# SCH_VTOL-FC_2024-12-10.net
KiCad netlist of a schematic drawn in EasyEDA
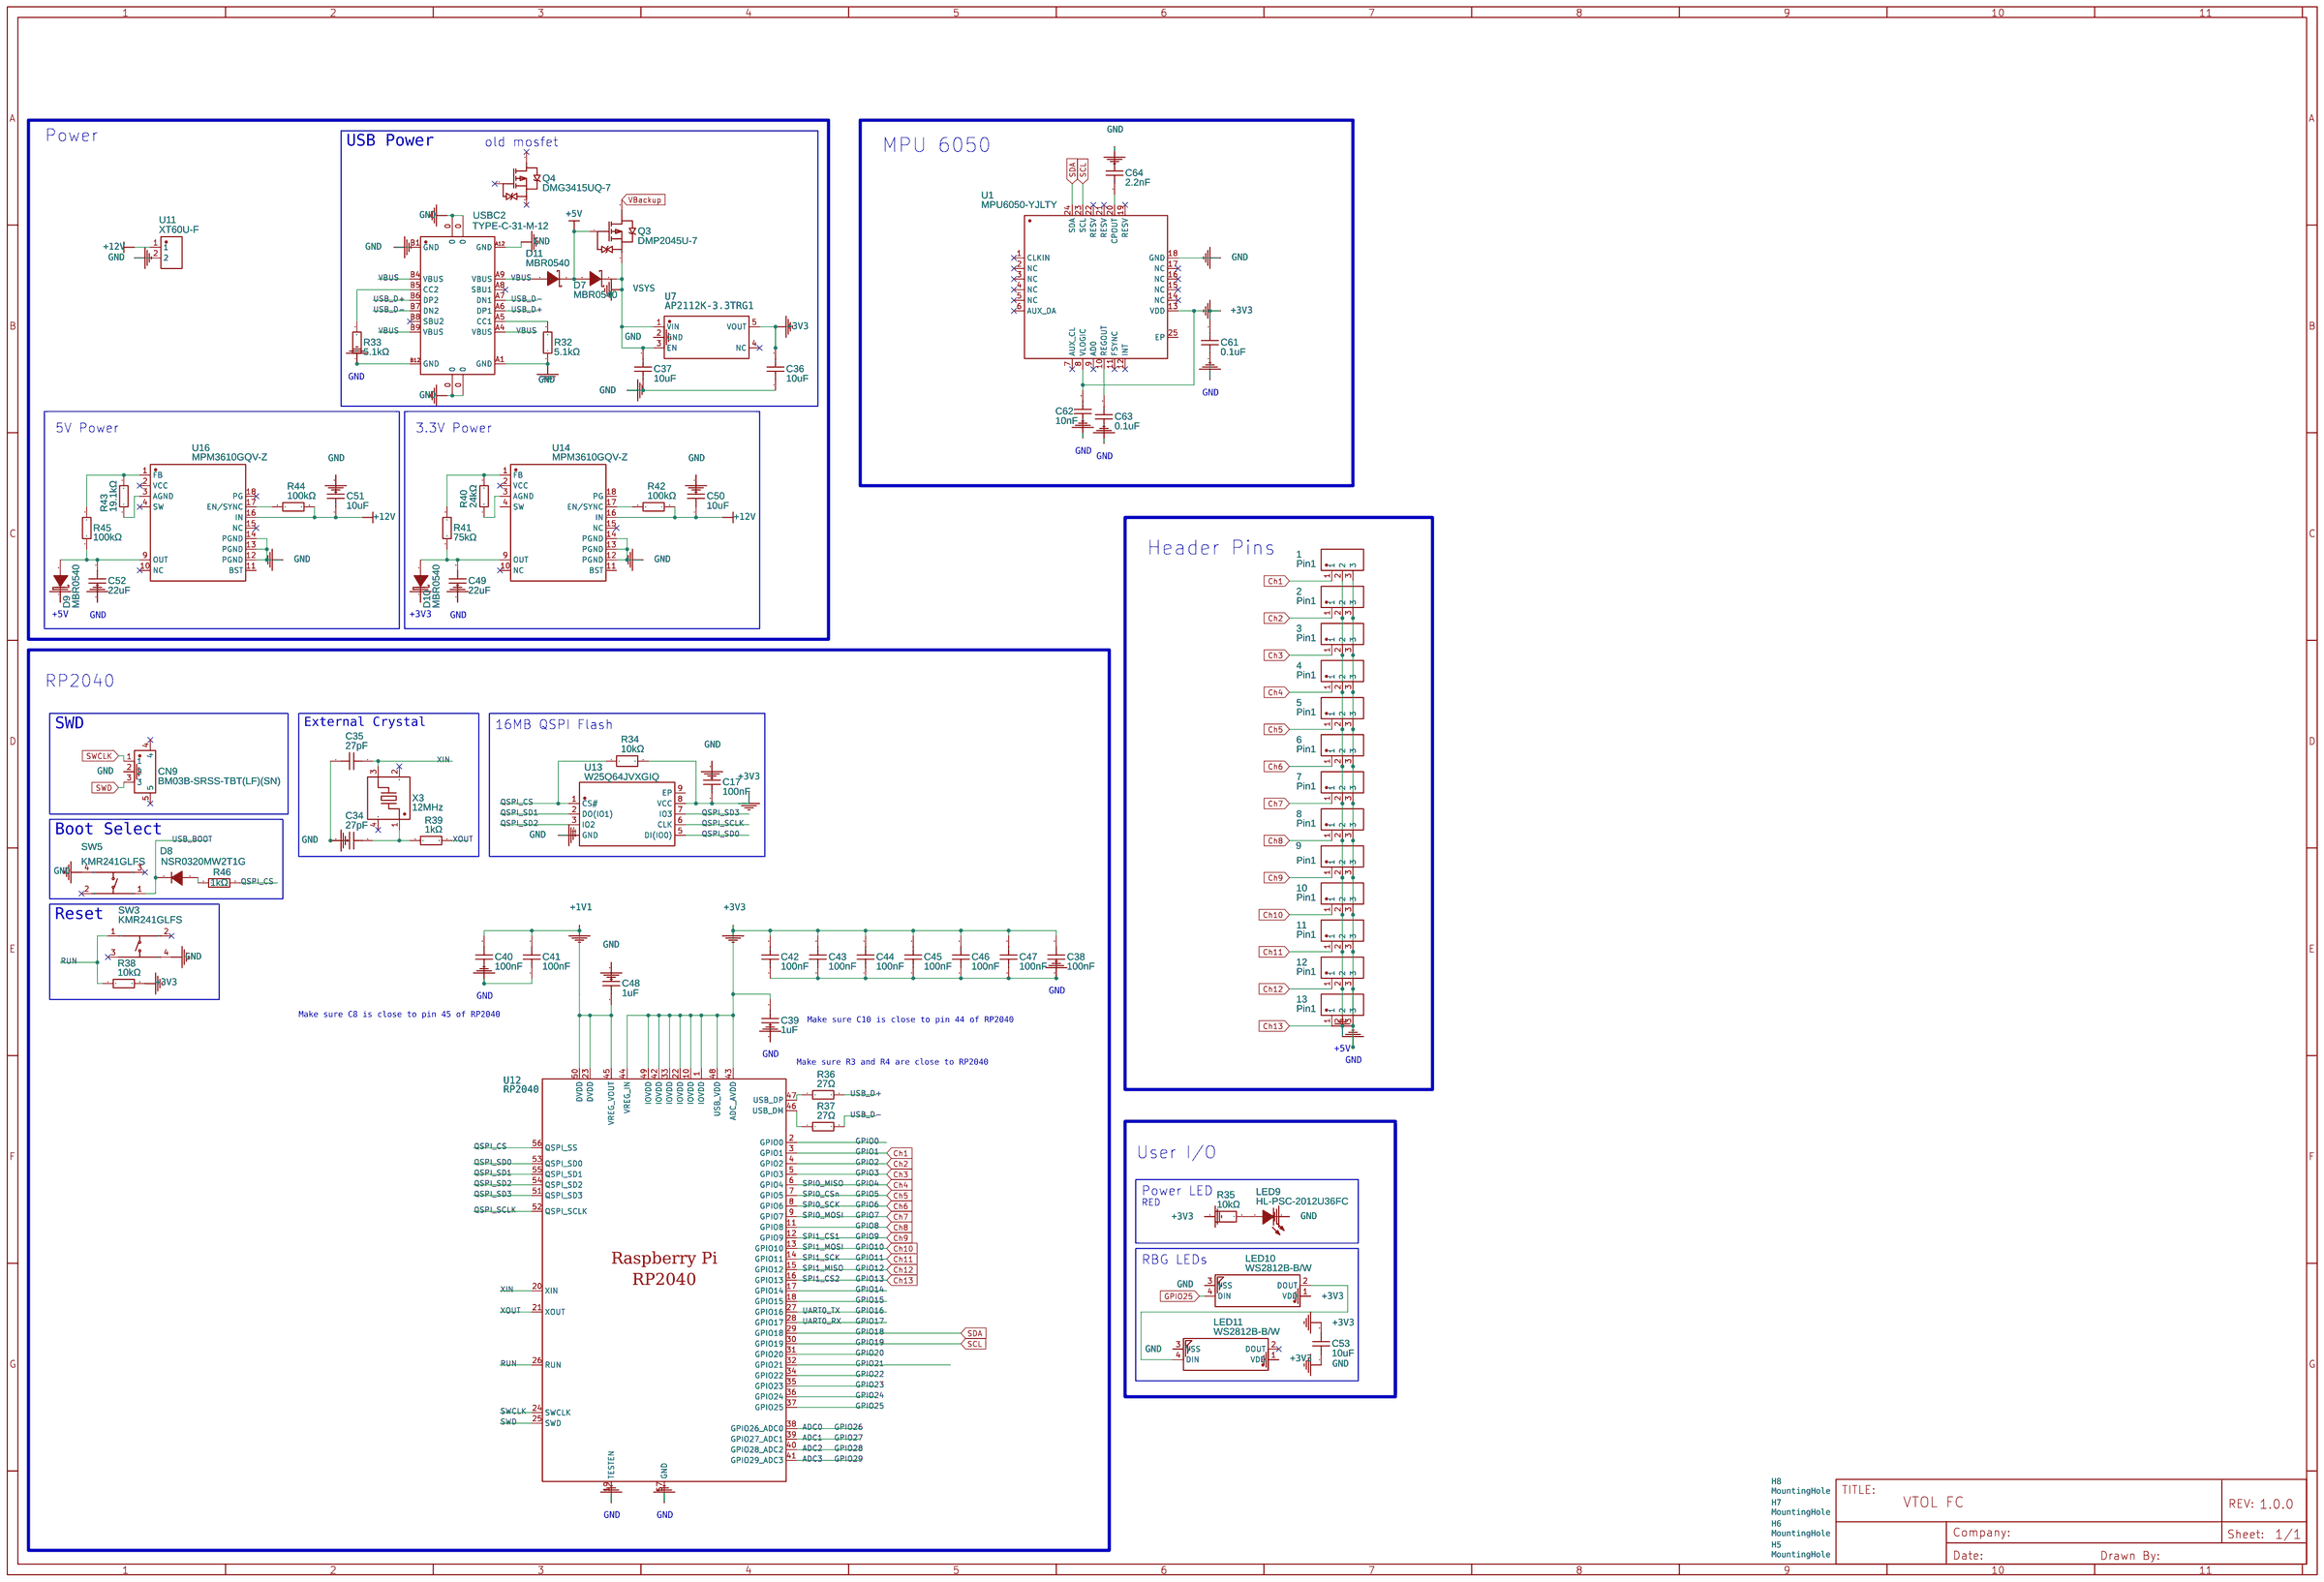
[diagram p0: schematic sheet]

(export (version "E")
  (design (tool "Eeschema 10.0.6"))
  (components
    (comp (ref "1")
      (value "Pin1")
      (fields
        (field (name "Manufacturer Part") "5-146277-3")
        (field (name "Manufacturer") "TE Connectivity(泰科电子)")
      )
      (libsource (lib "") (part "5-146277-3"))
    )
    (comp (ref "2")
      (value "Pin1")
      (fields
        (field (name "Manufacturer Part") "5-146277-3")
        (field (name "Manufacturer") "TE Connectivity(泰科电子)")
      )
      (libsource (lib "") (part "5-146277-3"))
    )
    (comp (ref "3")
      (value "Pin1")
      (fields
        (field (name "Manufacturer Part") "5-146277-3")
        (field (name "Manufacturer") "TE Connectivity(泰科电子)")
      )
      (libsource (lib "") (part "5-146277-3"))
    )
    (comp (ref "4")
      (value "Pin1")
      (fields
        (field (name "Manufacturer Part") "5-146277-3")
        (field (name "Manufacturer") "TE Connectivity(泰科电子)")
      )
      (libsource (lib "") (part "5-146277-3"))
    )
    (comp (ref "5")
      (value "Pin1")
      (fields
        (field (name "Manufacturer Part") "5-146277-3")
        (field (name "Manufacturer") "TE Connectivity(泰科电子)")
      )
      (libsource (lib "") (part "5-146277-3"))
    )
    (comp (ref "6")
      (value "Pin1")
      (fields
        (field (name "Manufacturer Part") "5-146277-3")
        (field (name "Manufacturer") "TE Connectivity(泰科电子)")
      )
      (libsource (lib "") (part "5-146277-3"))
    )
    (comp (ref "7")
      (value "Pin1")
      (fields
        (field (name "Manufacturer Part") "5-146277-3")
        (field (name "Manufacturer") "TE Connectivity(泰科电子)")
      )
      (libsource (lib "") (part "5-146277-3"))
    )
    (comp (ref "8")
      (value "Pin1")
      (fields
        (field (name "Manufacturer Part") "5-146277-3")
        (field (name "Manufacturer") "TE Connectivity(泰科电子)")
      )
      (libsource (lib "") (part "5-146277-3"))
    )
    (comp (ref "9")
      (value "Pin1")
      (fields
        (field (name "Manufacturer Part") "5-146277-3")
        (field (name "Manufacturer") "TE Connectivity(泰科电子)")
      )
      (libsource (lib "") (part "5-146277-3"))
    )
    (comp (ref "10")
      (value "Pin1")
      (fields
        (field (name "Manufacturer Part") "5-146277-3")
        (field (name "Manufacturer") "TE Connectivity(泰科电子)")
      )
      (libsource (lib "") (part "5-146277-3"))
    )
    (comp (ref "11")
      (value "Pin1")
      (fields
        (field (name "Manufacturer Part") "5-146277-3")
        (field (name "Manufacturer") "TE Connectivity(泰科电子)")
      )
      (libsource (lib "") (part "5-146277-3"))
    )
    (comp (ref "12")
      (value "Pin1")
      (fields
        (field (name "Manufacturer Part") "5-146277-3")
        (field (name "Manufacturer") "TE Connectivity(泰科电子)")
      )
      (libsource (lib "") (part "5-146277-3"))
    )
    (comp (ref "13")
      (value "Pin1")
      (fields
        (field (name "Manufacturer Part") "5-146277-3")
        (field (name "Manufacturer") "TE Connectivity(泰科电子)")
      )
      (libsource (lib "") (part "5-146277-3"))
    )
    (comp (ref "C17")
      (value "100nF")
      (fields
        (field (name "Manufacturer Part") "GCM155R71C104KA55D")
        (field (name "Manufacturer") "muRata(村田)")
      )
      (libsource (lib "") (part "GCM155R71C104KA55D"))
    )
    (comp (ref "C34")
      (value "27pF")
      (fields
        (field (name "Manufacturer Part") "GJM1555C1H270JB01D")
        (field (name "Manufacturer") "muRata(村田)")
      )
      (libsource (lib "") (part "GJM1555C1H270JB01D"))
    )
    (comp (ref "C35")
      (value "27pF")
      (fields
        (field (name "Manufacturer Part") "GJM1555C1H270JB01D")
        (field (name "Manufacturer") "muRata(村田)")
      )
      (libsource (lib "") (part "GJM1555C1H270JB01D"))
    )
    (comp (ref "C36")
      (value "10uF")
      (fields
        (field (name "Manufacturer Part") "CSA0603X5R106M6R3JT")
        (field (name "Manufacturer") "HRE(芯声)")
      )
      (libsource (lib "") (part "CSA0603X5R106M6R3JT"))
    )
    (comp (ref "C37")
      (value "10uF")
      (fields
        (field (name "Manufacturer Part") "CSA0603X5R106M6R3JT")
        (field (name "Manufacturer") "HRE(芯声)")
      )
      (libsource (lib "") (part "CSA0603X5R106M6R3JT"))
    )
    (comp (ref "C38")
      (value "100nF")
      (fields
        (field (name "Manufacturer Part") "GCM155R71C104KA55D")
        (field (name "Manufacturer") "muRata(村田)")
      )
      (libsource (lib "") (part "GCM155R71C104KA55D"))
    )
    (comp (ref "C39")
      (value "1uF")
      (fields
        (field (name "Manufacturer Part") "TCC0402X5R105K100AT")
        (field (name "Manufacturer") "CCTC(三环)")
      )
      (libsource (lib "") (part "TCC0402X5R105K100AT_1"))
    )
    (comp (ref "C40")
      (value "100nF")
      (fields
        (field (name "Manufacturer Part") "GCM155R71C104KA55D")
        (field (name "Manufacturer") "muRata(村田)")
      )
      (libsource (lib "") (part "GCM155R71C104KA55D"))
    )
    (comp (ref "C41")
      (value "100nF")
      (fields
        (field (name "Manufacturer Part") "GCM155R71C104KA55D")
        (field (name "Manufacturer") "muRata(村田)")
      )
      (libsource (lib "") (part "GCM155R71C104KA55D"))
    )
    (comp (ref "C42")
      (value "100nF")
      (fields
        (field (name "Manufacturer Part") "GCM155R71C104KA55D")
        (field (name "Manufacturer") "muRata(村田)")
      )
      (libsource (lib "") (part "GCM155R71C104KA55D"))
    )
    (comp (ref "C43")
      (value "100nF")
      (fields
        (field (name "Manufacturer Part") "GCM155R71C104KA55D")
        (field (name "Manufacturer") "muRata(村田)")
      )
      (libsource (lib "") (part "GCM155R71C104KA55D"))
    )
    (comp (ref "C44")
      (value "100nF")
      (fields
        (field (name "Manufacturer Part") "GCM155R71C104KA55D")
        (field (name "Manufacturer") "muRata(村田)")
      )
      (libsource (lib "") (part "GCM155R71C104KA55D"))
    )
    (comp (ref "C45")
      (value "100nF")
      (fields
        (field (name "Manufacturer Part") "GCM155R71C104KA55D")
        (field (name "Manufacturer") "muRata(村田)")
      )
      (libsource (lib "") (part "GCM155R71C104KA55D"))
    )
    (comp (ref "C46")
      (value "100nF")
      (fields
        (field (name "Manufacturer Part") "GCM155R71C104KA55D")
        (field (name "Manufacturer") "muRata(村田)")
      )
      (libsource (lib "") (part "GCM155R71C104KA55D"))
    )
    (comp (ref "C47")
      (value "100nF")
      (fields
        (field (name "Manufacturer Part") "GCM155R71C104KA55D")
        (field (name "Manufacturer") "muRata(村田)")
      )
      (libsource (lib "") (part "GCM155R71C104KA55D"))
    )
    (comp (ref "C48")
      (value "1uF")
      (fields
        (field (name "Manufacturer Part") "TCC0402X5R105K100AT")
        (field (name "Manufacturer") "CCTC(三环)")
      )
      (libsource (lib "") (part "TCC0402X5R105K100AT"))
    )
    (comp (ref "C49")
      (value "22uF")
      (fields
        (field (name "Manufacturer Part") "CL10A226MQ8NRNC")
        (field (name "Manufacturer") "SAMSUNG(三星)")
      )
      (libsource (lib "") (part "CL10A226MQ8NRNC"))
    )
    (comp (ref "C50")
      (value "10uF")
      (fields
        (field (name "Manufacturer Part") "CSA0603X5R106M6R3JT")
        (field (name "Manufacturer") "HRE(芯声)")
      )
      (libsource (lib "") (part "CSA0603X5R106M6R3JT"))
    )
    (comp (ref "C51")
      (value "10uF")
      (fields
        (field (name "Manufacturer Part") "CSA0603X5R106M6R3JT")
        (field (name "Manufacturer") "HRE(芯声)")
      )
      (libsource (lib "") (part "CSA0603X5R106M6R3JT"))
    )
    (comp (ref "C52")
      (value "22uF")
      (fields
        (field (name "Manufacturer Part") "CL10A226MQ8NRNC")
        (field (name "Manufacturer") "SAMSUNG(三星)")
      )
      (libsource (lib "") (part "CL10A226MQ8NRNC"))
    )
    (comp (ref "C53")
      (value "10uF")
      (fields
        (field (name "Manufacturer Part") "CSA0603X5R106M6R3JT")
        (field (name "Manufacturer") "HRE(芯声)")
      )
      (libsource (lib "") (part "CSA0603X5R106M6R3JT"))
    )
    (comp (ref "C61")
      (value "0.1uF")
      (fields (field (name "Manufacturer Part") "0603"))
      (libsource (lib "") (part "0603_C9900021180_1"))
    )
    (comp (ref "C62")
      (value "10nF")
      (fields (field (name "Manufacturer Part") "0603"))
      (libsource (lib "") (part "0603_C9900021180_1"))
    )
    (comp (ref "C63")
      (value "0.1uF")
      (fields (field (name "Manufacturer Part") "0603"))
      (libsource (lib "") (part "0603_C9900021180_1"))
    )
    (comp (ref "C64")
      (value "2.2nF")
      (fields (field (name "Manufacturer Part") "0603"))
      (libsource (lib "") (part "0603_C9900021180"))
    )
    (comp (ref "CN9")
      (value "BM03B-SRSS-TBT(LF)(SN)")
      (fields (field (name "Manufacturer") "JST"))
      (libsource (lib "") (part "BM03B-SRSS-TBT(LF)(SN)"))
    )
    (comp (ref "D7")
      (value "MBR0540")
      (fields (field (name "Manufacturer") "SHIKUES(时科)"))
      (libsource (lib "") (part "MBR0540"))
    )
    (comp (ref "D8")
      (value "NSR0320MW2T1G")
      (fields (field (name "Manufacturer") "onsemi(安森美)"))
      (libsource (lib "") (part "NSR0320MW2T1G"))
    )
    (comp (ref "D9")
      (value "MBR0540")
      (fields (field (name "Manufacturer") "SHIKUES(时科)"))
      (libsource (lib "") (part "MBR0540_1"))
    )
    (comp (ref "D10")
      (value "MBR0540")
      (fields (field (name "Manufacturer") "SHIKUES(时科)"))
      (libsource (lib "") (part "MBR0540_1"))
    )
    (comp (ref "D11")
      (value "MBR0540")
      (fields (field (name "Manufacturer") "SHIKUES(时科)"))
      (libsource (lib "") (part "MBR0540"))
    )
    (comp (ref "H5") (value "MountingHole") (libsource (lib "") (part "Unknown_1650_-25")))
    (comp (ref "H6") (value "MountingHole") (libsource (lib "") (part "Unknown_1650_-45")))
    (comp (ref "H7") (value "MountingHole") (libsource (lib "") (part "Unknown_1650_-65")))
    (comp (ref "H8") (value "MountingHole") (libsource (lib "") (part "Unknown_1650_-85")))
    (comp (ref "LED9")
      (value "HL-PSC-2012U36FC")
      (fields (field (name "Manufacturer") "HONGLITRONIC(鸿利光电)"))
      (libsource (lib "") (part "HL-PSC-2012U36FC"))
    )
    (comp (ref "LED10")
      (value "WS2812B-B/W")
      (fields (field (name "Manufacturer Part") "WS2812B-B/T") (field (name "Manufacturer") "worldsemi"))
      (libsource (lib "") (part "WS2812B-B/W"))
    )
    (comp (ref "LED11")
      (value "WS2812B-B/W")
      (fields (field (name "Manufacturer Part") "WS2812B-B/T") (field (name "Manufacturer") "worldsemi"))
      (libsource (lib "") (part "WS2812B-B/W"))
    )
    (comp (ref "Q3")
      (value "DMP2045U-7")
      (fields (field (name "Manufacturer") "DIODES(美台)"))
      (libsource (lib "") (part "DMP2045U-7"))
    )
    (comp (ref "Q4")
      (value "DMG3415UQ-7")
      (fields (field (name "Manufacturer") "DIODES(美台)"))
      (libsource (lib "") (part "DMG3415UQ-7"))
    )
    (comp (ref "R32")
      (value "5.1kΩ")
      (fields (field (name "Manufacturer Part") "ARG03DTC5101") (field (name "Manufacturer") "Viking(光颉)"))
      (libsource (lib "") (part "ARG03DTC5101"))
    )
    (comp (ref "R33")
      (value "5.1kΩ")
      (fields (field (name "Manufacturer Part") "ARG03DTC5101") (field (name "Manufacturer") "Viking(光颉)"))
      (libsource (lib "") (part "ARG03DTC5101"))
    )
    (comp (ref "R34")
      (value "10kΩ")
      (fields (field (name "Manufacturer Part") "FRC0603F1002TS") (field (name "Manufacturer") "FOJAN(富捷)"))
      (libsource (lib "") (part "FRC0603F1002TS"))
    )
    (comp (ref "R35")
      (value "10kΩ")
      (fields (field (name "Manufacturer Part") "FRC0603F1002TS") (field (name "Manufacturer") "FOJAN(富捷)"))
      (libsource (lib "") (part "FRC0603F1002TS"))
    )
    (comp (ref "R36")
      (value "27Ω")
      (fields
        (field (name "Manufacturer Part") "0402WGJ0270TCE")
        (field (name "Manufacturer") "UNI-ROYAL(厚声)")
      )
      (libsource (lib "") (part "0402WGJ0270TCE"))
    )
    (comp (ref "R37")
      (value "27Ω")
      (fields
        (field (name "Manufacturer Part") "0402WGJ0270TCE")
        (field (name "Manufacturer") "UNI-ROYAL(厚声)")
      )
      (libsource (lib "") (part "0402WGJ0270TCE"))
    )
    (comp (ref "R38")
      (value "10kΩ")
      (fields
        (field (name "Manufacturer Part") "0603WAF1002T5E")
        (field (name "Manufacturer") "UNI-ROYAL(厚声)")
      )
      (libsource (lib "") (part "0603WAF1002T5E"))
    )
    (comp (ref "R39")
      (value "1kΩ")
      (fields
        (field (name "Manufacturer Part") "0603WAF1001T5E")
        (field (name "Manufacturer") "UNI-ROYAL(厚声)")
      )
      (libsource (lib "") (part "0603WAF1001T5E"))
    )
    (comp (ref "R40")
      (value "24kΩ")
      (fields
        (field (name "Manufacturer Part") "0603WAF2402T5E")
        (field (name "Manufacturer") "UNI-ROYAL(厚声)")
      )
      (libsource (lib "") (part "0603WAF2402T5E"))
    )
    (comp (ref "R41")
      (value "75kΩ")
      (fields
        (field (name "Manufacturer Part") "0603WAF7502T5E")
        (field (name "Manufacturer") "UNI-ROYAL(厚声)")
      )
      (libsource (lib "") (part "0603WAF7502T5E"))
    )
    (comp (ref "R42")
      (value "100kΩ")
      (fields
        (field (name "Manufacturer Part") "0603WAF1003T5E")
        (field (name "Manufacturer") "UNI-ROYAL(厚声)")
      )
      (libsource (lib "") (part "0603WAF1003T5E"))
    )
    (comp (ref "R43")
      (value "19.1kΩ")
      (fields
        (field (name "Manufacturer Part") "RMC060319.1K1%N")
        (field (name "Manufacturer") "Tyohm(幸亚电阻)")
      )
      (libsource (lib "") (part "RMC060319.1K1%N"))
    )
    (comp (ref "R44")
      (value "100kΩ")
      (fields
        (field (name "Manufacturer Part") "0603WAF1003T5E")
        (field (name "Manufacturer") "UNI-ROYAL(厚声)")
      )
      (libsource (lib "") (part "0603WAF1003T5E"))
    )
    (comp (ref "R45")
      (value "100kΩ")
      (fields
        (field (name "Manufacturer Part") "0603WAF1003T5E")
        (field (name "Manufacturer") "UNI-ROYAL(厚声)")
      )
      (libsource (lib "") (part "0603WAF1003T5E_1"))
    )
    (comp (ref "R46")
      (value "1kΩ")
      (fields
        (field (name "Manufacturer Part") "0603WAF1001T5E")
        (field (name "Manufacturer") "UNI-ROYAL(厚声)")
      )
      (libsource (lib "") (part "0603WAF1001T5E"))
    )
    (comp (ref "SW3")
      (value "KMR241GLFS")
      (fields (field (name "Manufacturer") "C&K"))
      (libsource (lib "") (part "KMR241GLFS_1"))
    )
    (comp (ref "SW5")
      (value "KMR241GLFS")
      (fields (field (name "Manufacturer") "C&K"))
      (libsource (lib "") (part "KMR241GLFS"))
    )
    (comp (ref "U1") (value "MPU6050-YJLTY") (libsource (lib "") (part "MPU6050-YJLTY")))
    (comp (ref "U7")
      (value "AP2112K-3.3TRG1")
      (fields (field (name "Manufacturer") "DIODES"))
      (libsource (lib "") (part "AP2112K-3.3TRG1"))
    )
    (comp (ref "U11")
      (value "XT60U-F")
      (fields (field (name "Manufacturer") "AMASS(艾迈斯)"))
      (libsource (lib "") (part "XT60U-F"))
    )
    (comp (ref "U12")
      (value "RP2040")
      (fields (field (name "Manufacturer") "Raspberry Pi(树莓派)"))
      (libsource (lib "") (part "RP2040"))
    )
    (comp (ref "U13")
      (value "W25Q64JVXGIQ")
      (fields (field (name "Manufacturer") "WINBOND(华邦)"))
      (libsource (lib "") (part "W25Q64JVXGIQ"))
    )
    (comp (ref "U14")
      (value "MPM3610GQV-Z")
      (fields (field (name "Manufacturer") "MPS(芯源)"))
      (libsource (lib "") (part "MPM3610GQV-Z"))
    )
    (comp (ref "U16")
      (value "MPM3610GQV-Z")
      (fields (field (name "Manufacturer") "MPS(芯源)"))
      (libsource (lib "") (part "MPM3610GQV-Z"))
    )
    (comp (ref "USBC2")
      (value "TYPE-C-31-M-12")
      (fields (field (name "Manufacturer") "Rectangular Connectors - Contacts"))
      (libsource (lib "") (part "TYPE-C-31-M-12"))
    )
    (comp (ref "X3")
      (value "12MHz")
      (fields
        (field (name "Manufacturer Part") "NX3225SA-12MHz-STD-CSR-6")
        (field (name "Manufacturer") "NDK")
      )
      (libsource (lib "") (part "NX3225SA-12MHZ-STD-CSR-6"))
    )
  )
  (nets
    (net (code "1") (name "+1V1") (class "Default")
      (node (ref "C40") (pin "2") (pinfunction "2_2") (pintype "unspecified"))
      (node (ref "C41") (pin "2") (pinfunction "2_2") (pintype "unspecified"))
      (node (ref "C48") (pin "2") (pinfunction "2_2") (pintype "unspecified"))
      (node (ref "U12") (pin "23") (pinfunction "DVDD_23") (pintype "bidirectional"))
      (node (ref "U12") (pin "45") (pinfunction "VREG_VOUT_45") (pintype "bidirectional"))
      (node (ref "U12") (pin "50") (pinfunction "DVDD_50") (pintype "bidirectional"))
    )
    (net (code "2") (name "+3V3") (class "Default")
      (node (ref "C17") (pin "1") (pinfunction "1_1") (pintype "unspecified"))
      (node (ref "C36") (pin "2") (pinfunction "2_2") (pintype "unspecified"))
      (node (ref "C38") (pin "2") (pinfunction "2_2") (pintype "unspecified"))
      (node (ref "C39") (pin "2") (pinfunction "2_2") (pintype "unspecified"))
      (node (ref "C42") (pin "2") (pinfunction "2_2") (pintype "unspecified"))
      (node (ref "C43") (pin "2") (pinfunction "2_2") (pintype "unspecified"))
      (node (ref "C44") (pin "2") (pinfunction "2_2") (pintype "unspecified"))
      (node (ref "C45") (pin "2") (pinfunction "2_2") (pintype "unspecified"))
      (node (ref "C46") (pin "2") (pinfunction "2_2") (pintype "unspecified"))
      (node (ref "C47") (pin "2") (pinfunction "2_2") (pintype "unspecified"))
      (node (ref "C53") (pin "2") (pinfunction "2_2") (pintype "unspecified"))
      (node (ref "C61") (pin "2") (pinfunction "2_2") (pintype "unspecified"))
      (node (ref "C62") (pin "2") (pinfunction "2_2") (pintype "unspecified"))
      (node (ref "D10") (pin "1") (pinfunction "K_1") (pintype "unspecified"))
      (node (ref "LED10") (pin "1") (pinfunction "VDD_1") (pintype "unspecified"))
      (node (ref "LED11") (pin "1") (pinfunction "VDD_1") (pintype "unspecified"))
      (node (ref "R34") (pin "2") (pinfunction "2_2") (pintype "unspecified"))
      (node (ref "R35") (pin "1") (pinfunction "1_1") (pintype "unspecified"))
      (node (ref "R38") (pin "2") (pinfunction "2_2") (pintype "input"))
      (node (ref "U1") (pin "13") (pinfunction "VDD_13") (pintype "unspecified"))
      (node (ref "U1") (pin "8") (pinfunction "VLOGIC_8") (pintype "unspecified"))
      (node (ref "U12") (pin "1") (pinfunction "IOVDD_1") (pintype "bidirectional"))
      (node (ref "U12") (pin "10") (pinfunction "IOVDD_10") (pintype "bidirectional"))
      (node (ref "U12") (pin "22") (pinfunction "IOVDD_22") (pintype "bidirectional"))
      (node (ref "U12") (pin "33") (pinfunction "IOVDD_33") (pintype "bidirectional"))
      (node (ref "U12") (pin "42") (pinfunction "IOVDD_42") (pintype "bidirectional"))
      (node (ref "U12") (pin "43") (pinfunction "ADC_AVDD_43") (pintype "bidirectional"))
      (node (ref "U12") (pin "44") (pinfunction "VREG_IN_44") (pintype "bidirectional"))
      (node (ref "U12") (pin "48") (pinfunction "USB_VDD_48") (pintype "bidirectional"))
      (node (ref "U12") (pin "49") (pinfunction "IOVDD_49") (pintype "bidirectional"))
      (node (ref "U13") (pin "8") (pinfunction "VCC_8") (pintype "unspecified"))
      (node (ref "U7") (pin "5") (pinfunction "VOUT_5") (pintype "unspecified"))
    )
    (net (code "3") (name "+5V") (class "Default")
      (node (ref "1") (pin "2") (pinfunction "2_2") (pintype "unspecified"))
      (node (ref "10") (pin "2") (pinfunction "2_2") (pintype "unspecified"))
      (node (ref "11") (pin "2") (pinfunction "2_2") (pintype "unspecified"))
      (node (ref "12") (pin "2") (pinfunction "2_2") (pintype "unspecified"))
      (node (ref "13") (pin "2") (pinfunction "2_2") (pintype "unspecified"))
      (node (ref "2") (pin "2") (pinfunction "2_2") (pintype "unspecified"))
      (node (ref "3") (pin "2") (pinfunction "2_2") (pintype "unspecified"))
      (node (ref "4") (pin "2") (pinfunction "2_2") (pintype "unspecified"))
      (node (ref "5") (pin "2") (pinfunction "2_2") (pintype "unspecified"))
      (node (ref "6") (pin "2") (pinfunction "2_2") (pintype "unspecified"))
      (node (ref "7") (pin "2") (pinfunction "2_2") (pintype "unspecified"))
      (node (ref "8") (pin "2") (pinfunction "2_2") (pintype "unspecified"))
      (node (ref "9") (pin "2") (pinfunction "2_2") (pintype "unspecified"))
      (node (ref "D11") (pin "1") (pinfunction "K_1") (pintype "unspecified"))
      (node (ref "D7") (pin "2") (pinfunction "A_2") (pintype "unspecified"))
      (node (ref "D9") (pin "1") (pinfunction "K_1") (pintype "unspecified"))
      (node (ref "Q3") (pin "1") (pinfunction "G_1") (pintype "unspecified"))
    )
    (net (code "4") (name "+12V") (class "Default")
      (node (ref "C50") (pin "1") (pinfunction "1_1") (pintype "unspecified"))
      (node (ref "C51") (pin "1") (pinfunction "1_1") (pintype "unspecified"))
      (node (ref "R42") (pin "1") (pinfunction "1_1") (pintype "input"))
      (node (ref "R44") (pin "1") (pinfunction "1_1") (pintype "input"))
      (node (ref "U11") (pin "1") (pinfunction "1_1") (pintype "unspecified"))
      (node (ref "U14") (pin "16") (pinfunction "IN_16") (pintype "unspecified"))
      (node (ref "U16") (pin "16") (pinfunction "IN_16") (pintype "unspecified"))
    )
    (net (code "5") (name "/ADC0") (class "Default")
      (node (ref "U12") (pin "38") (pinfunction "GPIO26_ADC0_38") (pintype "bidirectional"))
    )
    (net (code "6") (name "/ADC1") (class "Default")
      (node (ref "U12") (pin "39") (pinfunction "GPIO27_ADC1_39") (pintype "bidirectional"))
    )
    (net (code "7") (name "/ADC2") (class "Default")
      (node (ref "U12") (pin "40") (pinfunction "GPIO28_ADC2_40") (pintype "bidirectional"))
    )
    (net (code "8") (name "/ADC3") (class "Default")
      (node (ref "U12") (pin "41") (pinfunction "GPIO29_ADC3_41") (pintype "bidirectional"))
    )
    (net (code "9") (name "/GPIO0") (class "Default")
      (node (ref "U12") (pin "2") (pinfunction "GPIO0_2") (pintype "bidirectional"))
    )
    (net (code "10") (name "/GPIO14") (class "Default")
      (node (ref "U12") (pin "17") (pinfunction "GPIO14_17") (pintype "bidirectional"))
    )
    (net (code "11") (name "/GPIO15") (class "Default")
      (node (ref "U12") (pin "18") (pinfunction "GPIO15_18") (pintype "bidirectional"))
    )
    (net (code "12") (name "/GPIO16") (class "Default")
      (node (ref "U12") (pin "27") (pinfunction "GPIO16_27") (pintype "bidirectional"))
    )
    (net (code "13") (name "/GPIO17") (class "Default")
      (node (ref "U12") (pin "28") (pinfunction "GPIO17_28") (pintype "bidirectional"))
    )
    (net (code "14") (name "/GPIO20") (class "Default")
      (node (ref "U12") (pin "31") (pinfunction "GPIO20_31") (pintype "bidirectional"))
    )
    (net (code "15") (name "/GPIO21") (class "Default")
      (node (ref "U12") (pin "32") (pinfunction "GPIO21_32") (pintype "bidirectional"))
    )
    (net (code "16") (name "/GPIO22") (class "Default")
      (node (ref "U12") (pin "34") (pinfunction "GPIO22_34") (pintype "bidirectional"))
    )
    (net (code "17") (name "/GPIO23") (class "Default")
      (node (ref "U12") (pin "35") (pinfunction "GPIO23_35") (pintype "bidirectional"))
    )
    (net (code "18") (name "/GPIO24") (class "Default")
      (node (ref "U12") (pin "36") (pinfunction "GPIO24_36") (pintype "bidirectional"))
    )
    (net (code "19") (name "/QSPI_CS") (class "Default")
      (node (ref "R34") (pin "1") (pinfunction "1_1") (pintype "unspecified"))
      (node (ref "R46") (pin "2") (pinfunction "2_2") (pintype "input"))
      (node (ref "U12") (pin "56") (pinfunction "QSPI_SS_56") (pintype "bidirectional"))
      (node (ref "U13") (pin "1") (pinfunction "CS#_1") (pintype "unspecified"))
    )
    (net (code "20") (name "/QSPI_SCLK") (class "Default")
      (node (ref "U12") (pin "52") (pinfunction "QSPI_SCLK_52") (pintype "output"))
      (node (ref "U13") (pin "6") (pinfunction "CLK_6") (pintype "unspecified"))
    )
    (net (code "21") (name "/QSPI_SD0") (class "Default")
      (node (ref "U12") (pin "53") (pinfunction "QSPI_SD0_53") (pintype "bidirectional"))
      (node (ref "U13") (pin "5") (pinfunction "DI(IO0)_5") (pintype "unspecified"))
    )
    (net (code "22") (name "/QSPI_SD1") (class "Default")
      (node (ref "U12") (pin "55") (pinfunction "QSPI_SD1_55") (pintype "bidirectional"))
      (node (ref "U13") (pin "2") (pinfunction "DO(IO1)_2") (pintype "unspecified"))
    )
    (net (code "23") (name "/QSPI_SD2") (class "Default")
      (node (ref "U12") (pin "54") (pinfunction "QSPI_SD2_54") (pintype "bidirectional"))
      (node (ref "U13") (pin "3") (pinfunction "IO2_3") (pintype "unspecified"))
    )
    (net (code "24") (name "/QSPI_SD3") (class "Default")
      (node (ref "U12") (pin "51") (pinfunction "QSPI_SD3_51") (pintype "bidirectional"))
      (node (ref "U13") (pin "7") (pinfunction "IO3_7") (pintype "unspecified"))
    )
    (net (code "25") (name "/RUN") (class "Default")
      (node (ref "R38") (pin "1") (pinfunction "1_1") (pintype "input"))
      (node (ref "SW3") (pin "1") (pinfunction "1_1") (pintype "unspecified"))
      (node (ref "U12") (pin "26") (pinfunction "RUN_26") (pintype "input"))
    )
    (net (code "26") (name "/USB_BOOT") (class "Default")
      (node (ref "D8") (pin "1") (pinfunction "C_1") (pintype "unspecified"))
      (node (ref "SW5") (pin "1") (pinfunction "1_1") (pintype "unspecified"))
    )
    (net (code "27") (name "/USB_D+") (class "Default")
      (node (ref "R36") (pin "2") (pinfunction "2_2") (pintype "input"))
      (node (ref "USBC2") (pin "A6") (pinfunction "DP1_A6") (pintype "unspecified"))
      (node (ref "USBC2") (pin "B6") (pinfunction "DP2_B6") (pintype "unspecified"))
    )
    (net (code "28") (name "/USB_D-") (class "Default")
      (node (ref "R37") (pin "2") (pinfunction "2_2") (pintype "input"))
      (node (ref "USBC2") (pin "A7") (pinfunction "DN1_A7") (pintype "unspecified"))
      (node (ref "USBC2") (pin "B7") (pinfunction "DN2_B7") (pintype "unspecified"))
    )
    (net (code "29") (name "/VBUS") (class "Default")
      (node (ref "D11") (pin "2") (pinfunction "A_2") (pintype "unspecified"))
      (node (ref "USBC2") (pin "A4") (pinfunction "VBUS_A4") (pintype "unspecified"))
      (node (ref "USBC2") (pin "A9") (pinfunction "VBUS_A9") (pintype "unspecified"))
      (node (ref "USBC2") (pin "B4") (pinfunction "VBUS_B4") (pintype "unspecified"))
      (node (ref "USBC2") (pin "B9") (pinfunction "VBUS_B9") (pintype "unspecified"))
    )
    (net (code "30") (name "/XIN") (class "Default")
      (node (ref "C35") (pin "2") (pinfunction "2_2") (pintype "unspecified"))
      (node (ref "U12") (pin "20") (pinfunction "XIN_20") (pintype "input"))
      (node (ref "X3") (pin "3") (pinfunction "3_3") (pintype "input"))
    )
    (net (code "31") (name "/XOUT") (class "Default")
      (node (ref "R39") (pin "2") (pinfunction "2_2") (pintype "input"))
      (node (ref "U12") (pin "21") (pinfunction "XOUT_21") (pintype "unspecified"))
    )
    (net (code "32") (name "Ch1") (class "Default")
      (node (ref "1") (pin "1") (pinfunction "1_1") (pintype "unspecified"))
      (node (ref "U12") (pin "3") (pinfunction "GPIO1_3") (pintype "bidirectional"))
    )
    (net (code "33") (name "Ch2") (class "Default")
      (node (ref "2") (pin "1") (pinfunction "1_1") (pintype "unspecified"))
      (node (ref "U12") (pin "4") (pinfunction "GPIO2_4") (pintype "bidirectional"))
    )
    (net (code "34") (name "Ch3") (class "Default")
      (node (ref "3") (pin "1") (pinfunction "1_1") (pintype "unspecified"))
      (node (ref "U12") (pin "5") (pinfunction "GPIO3_5") (pintype "bidirectional"))
    )
    (net (code "35") (name "Ch4") (class "Default")
      (node (ref "4") (pin "1") (pinfunction "1_1") (pintype "unspecified"))
      (node (ref "U12") (pin "6") (pinfunction "GPIO4_6") (pintype "bidirectional"))
    )
    (net (code "36") (name "Ch5") (class "Default")
      (node (ref "5") (pin "1") (pinfunction "1_1") (pintype "unspecified"))
      (node (ref "U12") (pin "7") (pinfunction "GPIO5_7") (pintype "bidirectional"))
    )
    (net (code "37") (name "Ch6") (class "Default")
      (node (ref "6") (pin "1") (pinfunction "1_1") (pintype "unspecified"))
      (node (ref "U12") (pin "8") (pinfunction "GPIO6_8") (pintype "bidirectional"))
    )
    (net (code "38") (name "Ch7") (class "Default")
      (node (ref "7") (pin "1") (pinfunction "1_1") (pintype "unspecified"))
      (node (ref "U12") (pin "9") (pinfunction "GPIO7_9") (pintype "bidirectional"))
    )
    (net (code "39") (name "Ch8") (class "Default")
      (node (ref "8") (pin "1") (pinfunction "1_1") (pintype "unspecified"))
      (node (ref "U12") (pin "11") (pinfunction "GPIO8_11") (pintype "bidirectional"))
    )
    (net (code "40") (name "Ch9") (class "Default")
      (node (ref "9") (pin "1") (pinfunction "1_1") (pintype "unspecified"))
      (node (ref "U12") (pin "12") (pinfunction "GPIO9_12") (pintype "bidirectional"))
    )
    (net (code "41") (name "Ch10") (class "Default")
      (node (ref "10") (pin "1") (pinfunction "1_1") (pintype "unspecified"))
      (node (ref "U12") (pin "13") (pinfunction "GPIO10_13") (pintype "bidirectional"))
    )
    (net (code "42") (name "Ch11") (class "Default")
      (node (ref "11") (pin "1") (pinfunction "1_1") (pintype "unspecified"))
      (node (ref "U12") (pin "14") (pinfunction "GPIO11_14") (pintype "bidirectional"))
    )
    (net (code "43") (name "Ch12") (class "Default")
      (node (ref "12") (pin "1") (pinfunction "1_1") (pintype "unspecified"))
      (node (ref "U12") (pin "15") (pinfunction "GPIO12_15") (pintype "bidirectional"))
    )
    (net (code "44") (name "Ch13") (class "Default")
      (node (ref "13") (pin "1") (pinfunction "1_1") (pintype "unspecified"))
      (node (ref "U12") (pin "16") (pinfunction "GPIO13_16") (pintype "bidirectional"))
    )
    (net (code "45") (name "GND") (class "Default")
      (node (ref "1") (pin "3") (pinfunction "3_3") (pintype "unspecified"))
      (node (ref "10") (pin "3") (pinfunction "3_3") (pintype "unspecified"))
      (node (ref "11") (pin "3") (pinfunction "3_3") (pintype "unspecified"))
      (node (ref "12") (pin "3") (pinfunction "3_3") (pintype "unspecified"))
      (node (ref "13") (pin "3") (pinfunction "3_3") (pintype "unspecified"))
      (node (ref "2") (pin "3") (pinfunction "3_3") (pintype "unspecified"))
      (node (ref "3") (pin "3") (pinfunction "3_3") (pintype "unspecified"))
      (node (ref "4") (pin "3") (pinfunction "3_3") (pintype "unspecified"))
      (node (ref "5") (pin "3") (pinfunction "3_3") (pintype "unspecified"))
      (node (ref "6") (pin "3") (pinfunction "3_3") (pintype "unspecified"))
      (node (ref "7") (pin "3") (pinfunction "3_3") (pintype "unspecified"))
      (node (ref "8") (pin "3") (pinfunction "3_3") (pintype "unspecified"))
      (node (ref "9") (pin "3") (pinfunction "3_3") (pintype "unspecified"))
      (node (ref "C17") (pin "2") (pinfunction "2_2") (pintype "unspecified"))
      (node (ref "C34") (pin "1") (pinfunction "1_1") (pintype "unspecified"))
      (node (ref "C35") (pin "1") (pinfunction "1_1") (pintype "unspecified"))
      (node (ref "C36") (pin "1") (pinfunction "1_1") (pintype "unspecified"))
      (node (ref "C37") (pin "1") (pinfunction "1_1") (pintype "unspecified"))
      (node (ref "C38") (pin "1") (pinfunction "1_1") (pintype "unspecified"))
      (node (ref "C39") (pin "1") (pinfunction "1_1") (pintype "unspecified"))
      (node (ref "C40") (pin "1") (pinfunction "1_1") (pintype "unspecified"))
      (node (ref "C41") (pin "1") (pinfunction "1_1") (pintype "unspecified"))
      (node (ref "C42") (pin "1") (pinfunction "1_1") (pintype "unspecified"))
      (node (ref "C43") (pin "1") (pinfunction "1_1") (pintype "unspecified"))
      (node (ref "C44") (pin "1") (pinfunction "1_1") (pintype "unspecified"))
      (node (ref "C45") (pin "1") (pinfunction "1_1") (pintype "unspecified"))
      (node (ref "C46") (pin "1") (pinfunction "1_1") (pintype "unspecified"))
      (node (ref "C47") (pin "1") (pinfunction "1_1") (pintype "unspecified"))
      (node (ref "C48") (pin "1") (pinfunction "1_1") (pintype "unspecified"))
      (node (ref "C49") (pin "1") (pinfunction "1_1") (pintype "unspecified"))
      (node (ref "C50") (pin "2") (pinfunction "2_2") (pintype "unspecified"))
      (node (ref "C51") (pin "2") (pinfunction "2_2") (pintype "unspecified"))
      (node (ref "C52") (pin "1") (pinfunction "1_1") (pintype "unspecified"))
      (node (ref "C53") (pin "1") (pinfunction "1_1") (pintype "unspecified"))
      (node (ref "C61") (pin "1") (pinfunction "1_1") (pintype "unspecified"))
      (node (ref "C62") (pin "1") (pinfunction "1_1") (pintype "unspecified"))
      (node (ref "C63") (pin "1") (pinfunction "1_1") (pintype "unspecified"))
      (node (ref "C64") (pin "1") (pinfunction "1_1") (pintype "unspecified"))
      (node (ref "CN9") (pin "2") (pinfunction "2_2") (pintype "unspecified"))
      (node (ref "LED10") (pin "3") (pinfunction "VSS_3") (pintype "unspecified"))
      (node (ref "LED11") (pin "3") (pinfunction "VSS_3") (pintype "unspecified"))
      (node (ref "LED9") (pin "1") (pinfunction "C_1") (pintype "unspecified"))
      (node (ref "R32") (pin "1") (pinfunction "1_1") (pintype "unspecified"))
      (node (ref "R33") (pin "1") (pinfunction "1_1") (pintype "unspecified"))
      (node (ref "SW3") (pin "4") (pinfunction "4_4") (pintype "unspecified"))
      (node (ref "SW5") (pin "4") (pinfunction "4_4") (pintype "unspecified"))
      (node (ref "U1") (pin "18") (pinfunction "GND_18") (pintype "unspecified"))
      (node (ref "U11") (pin "2") (pinfunction "2_2") (pintype "unspecified"))
      (node (ref "U12") (pin "19") (pinfunction "TESTEN_19") (pintype "unspecified"))
      (node (ref "U12") (pin "57") (pinfunction "GND_57") (pintype "bidirectional"))
      (node (ref "U13") (pin "4") (pinfunction "GND_4") (pintype "unspecified"))
      (node (ref "U14") (pin "12") (pinfunction "PGND_12") (pintype "unspecified"))
      (node (ref "U14") (pin "13") (pinfunction "PGND_13") (pintype "unspecified"))
      (node (ref "U14") (pin "14") (pinfunction "PGND_14") (pintype "unspecified"))
      (node (ref "U16") (pin "12") (pinfunction "PGND_12") (pintype "unspecified"))
      (node (ref "U16") (pin "13") (pinfunction "PGND_13") (pintype "unspecified"))
      (node (ref "U16") (pin "14") (pinfunction "PGND_14") (pintype "unspecified"))
      (node (ref "U7") (pin "2") (pinfunction "GND_2") (pintype "unspecified"))
      (node (ref "USBC2") (pin "0") (pinfunction "0_0") (pintype "unspecified"))
      (node (ref "USBC2") (pin "A1") (pinfunction "GND_A1") (pintype "unspecified"))
      (node (ref "USBC2") (pin "A12") (pinfunction "GND_A12") (pintype "unspecified"))
      (node (ref "USBC2") (pin "B1") (pinfunction "GND_B1") (pintype "unspecified"))
      (node (ref "USBC2") (pin "B12") (pinfunction "GND_B12") (pintype "unspecified"))
    )
    (net (code "46") (name "GPIO25") (class "Default")
      (node (ref "LED10") (pin "4") (pinfunction "DIN_4") (pintype "unspecified"))
      (node (ref "U12") (pin "37") (pinfunction "GPIO25_37") (pintype "bidirectional"))
    )
    (net (code "47") (name "Net-(C34-Pad2)") (class "Default")
      (node (ref "C34") (pin "2") (pinfunction "2_2") (pintype "unspecified"))
      (node (ref "R39") (pin "1") (pinfunction "1_1") (pintype "input"))
      (node (ref "X3") (pin "1") (pinfunction "1_1") (pintype "input"))
    )
    (net (code "48") (name "Net-(D8-A)") (class "Default")
      (node (ref "D8") (pin "2") (pinfunction "A_2") (pintype "unspecified"))
      (node (ref "R46") (pin "1") (pinfunction "1_1") (pintype "input"))
    )
    (net (code "49") (name "Net-(D9-A)") (class "Default")
      (node (ref "C52") (pin "2") (pinfunction "2_2") (pintype "unspecified"))
      (node (ref "D9") (pin "2") (pinfunction "A_2") (pintype "unspecified"))
      (node (ref "R45") (pin "1") (pinfunction "1_1") (pintype "input"))
      (node (ref "U16") (pin "9") (pinfunction "OUT_9") (pintype "unspecified"))
    )
    (net (code "50") (name "Net-(D10-A)") (class "Default")
      (node (ref "C49") (pin "2") (pinfunction "2_2") (pintype "unspecified"))
      (node (ref "D10") (pin "2") (pinfunction "A_2") (pintype "unspecified"))
      (node (ref "R41") (pin "1") (pinfunction "1_1") (pintype "input"))
      (node (ref "U14") (pin "9") (pinfunction "OUT_9") (pintype "unspecified"))
    )
    (net (code "51") (name "Net-(LED9-A)") (class "Default")
      (node (ref "LED9") (pin "2") (pinfunction "A_2") (pintype "unspecified"))
      (node (ref "R35") (pin "2") (pinfunction "2_2") (pintype "unspecified"))
    )
    (net (code "52") (name "Net-(LED10-DOUT)") (class "Default")
      (node (ref "LED10") (pin "2") (pinfunction "DOUT_2") (pintype "unspecified"))
      (node (ref "LED11") (pin "4") (pinfunction "DIN_4") (pintype "unspecified"))
    )
    (net (code "53") (name "Net-(U1-CPOUT)") (class "Default")
      (node (ref "C64") (pin "2") (pinfunction "2_2") (pintype "unspecified"))
      (node (ref "U1") (pin "20") (pinfunction "CPOUT_20") (pintype "unspecified"))
    )
    (net (code "54") (name "Net-(U1-REGOUT)") (class "Default")
      (node (ref "C63") (pin "2") (pinfunction "2_2") (pintype "unspecified"))
      (node (ref "U1") (pin "10") (pinfunction "REGOUT_10") (pintype "unspecified"))
    )
    (net (code "55") (name "Net-(U12-USB_DM)") (class "Default")
      (node (ref "R37") (pin "1") (pinfunction "1_1") (pintype "input"))
      (node (ref "U12") (pin "46") (pinfunction "USB_DM_46") (pintype "bidirectional"))
    )
    (net (code "56") (name "Net-(U12-USB_DP)") (class "Default")
      (node (ref "R36") (pin "1") (pinfunction "1_1") (pintype "input"))
      (node (ref "U12") (pin "47") (pinfunction "USB_DP_47") (pintype "bidirectional"))
    )
    (net (code "57") (name "Net-(U14-AGND)") (class "Default")
      (node (ref "R40") (pin "1") (pinfunction "1_1") (pintype "input"))
      (node (ref "U14") (pin "3") (pinfunction "AGND_3") (pintype "unspecified"))
    )
    (net (code "58") (name "Net-(U14-EN{slash}SYNC)") (class "Default")
      (node (ref "R42") (pin "2") (pinfunction "2_2") (pintype "input"))
      (node (ref "U14") (pin "17") (pinfunction "EN/SYNC_17") (pintype "unspecified"))
    )
    (net (code "59") (name "Net-(U14-FB)") (class "Default")
      (node (ref "R40") (pin "2") (pinfunction "2_2") (pintype "input"))
      (node (ref "R41") (pin "2") (pinfunction "2_2") (pintype "input"))
      (node (ref "U14") (pin "1") (pinfunction "FB_1") (pintype "unspecified"))
    )
    (net (code "60") (name "Net-(U16-AGND)") (class "Default")
      (node (ref "R43") (pin "1") (pinfunction "1_1") (pintype "unspecified"))
      (node (ref "U16") (pin "3") (pinfunction "AGND_3") (pintype "unspecified"))
    )
    (net (code "61") (name "Net-(U16-EN{slash}SYNC)") (class "Default")
      (node (ref "R44") (pin "2") (pinfunction "2_2") (pintype "input"))
      (node (ref "U16") (pin "17") (pinfunction "EN/SYNC_17") (pintype "unspecified"))
    )
    (net (code "62") (name "Net-(U16-FB)") (class "Default")
      (node (ref "R43") (pin "2") (pinfunction "2_2") (pintype "unspecified"))
      (node (ref "R45") (pin "2") (pinfunction "2_2") (pintype "input"))
      (node (ref "U16") (pin "1") (pinfunction "FB_1") (pintype "unspecified"))
    )
    (net (code "63") (name "Net-(USBC2-CC1)") (class "Default")
      (node (ref "R32") (pin "2") (pinfunction "2_2") (pintype "unspecified"))
      (node (ref "USBC2") (pin "A5") (pinfunction "CC1_A5") (pintype "unspecified"))
    )
    (net (code "64") (name "Net-(USBC2-CC2)") (class "Default")
      (node (ref "R33") (pin "2") (pinfunction "2_2") (pintype "unspecified"))
      (node (ref "USBC2") (pin "B5") (pinfunction "CC2_B5") (pintype "unspecified"))
    )
    (net (code "65") (name "SCL") (class "Default")
      (node (ref "U1") (pin "23") (pinfunction "SCL_23") (pintype "unspecified"))
      (node (ref "U12") (pin "30") (pinfunction "GPIO19_30") (pintype "bidirectional"))
    )
    (net (code "66") (name "SDA") (class "Default")
      (node (ref "U1") (pin "24") (pinfunction "SDA_24") (pintype "unspecified"))
      (node (ref "U12") (pin "29") (pinfunction "GPIO18_29") (pintype "bidirectional"))
    )
    (net (code "67") (name "SWCLK") (class "Default")
      (node (ref "CN9") (pin "1") (pinfunction "1_1") (pintype "unspecified"))
      (node (ref "U12") (pin "24") (pinfunction "SWCLK_24") (pintype "output"))
    )
    (net (code "68") (name "SWD") (class "Default")
      (node (ref "CN9") (pin "3") (pinfunction "3_3") (pintype "unspecified"))
      (node (ref "U12") (pin "25") (pinfunction "SWD_25") (pintype "bidirectional"))
    )
    (net (code "69") (name "VBackup") (class "Default")
      (node (ref "Q3") (pin "2") (pinfunction "D_2") (pintype "unspecified"))
    )
    (net (code "70") (name "VSYS") (class "Default")
      (node (ref "C37") (pin "2") (pinfunction "2_2") (pintype "unspecified"))
      (node (ref "D7") (pin "1") (pinfunction "K_1") (pintype "unspecified"))
      (node (ref "Q3") (pin "3") (pinfunction "S_3") (pintype "unspecified"))
      (node (ref "U7") (pin "1") (pinfunction "VIN_1") (pintype "unspecified"))
      (node (ref "U7") (pin "3") (pinfunction "EN_3") (pintype "unspecified"))
    )
    (net (code "71") (name "unconnected-(CN9-Pad4)") (class "Default")
      (node (ref "CN9") (pin "4") (pinfunction "4_4") (pintype "unspecified+no_connect"))
    )
    (net (code "72") (name "unconnected-(CN9-Pad5)") (class "Default")
      (node (ref "CN9") (pin "5") (pinfunction "5_5") (pintype "unspecified+no_connect"))
    )
    (net (code "73") (name "unconnected-(LED11-DOUT-Pad2)") (class "Default")
      (node (ref "LED11") (pin "2") (pinfunction "DOUT_2") (pintype "unspecified+no_connect"))
    )
    (net (code "74") (name "unconnected-(Q4-D-Pad3)") (class "Default")
      (node (ref "Q4") (pin "3") (pinfunction "D_3") (pintype "unspecified+no_connect"))
    )
    (net (code "75") (name "unconnected-(Q4-G-Pad1)") (class "Default")
      (node (ref "Q4") (pin "1") (pinfunction "G_1") (pintype "unspecified+no_connect"))
    )
    (net (code "76") (name "unconnected-(Q4-S-Pad2)") (class "Default")
      (node (ref "Q4") (pin "2") (pinfunction "S_2") (pintype "unspecified+no_connect"))
    )
    (net (code "77") (name "unconnected-(SW3-Pad2)") (class "Default")
      (node (ref "SW3") (pin "2") (pinfunction "2_2") (pintype "unspecified+no_connect"))
    )
    (net (code "78") (name "unconnected-(SW3-Pad3)") (class "Default")
      (node (ref "SW3") (pin "3") (pinfunction "3_3") (pintype "unspecified+no_connect"))
    )
    (net (code "79") (name "unconnected-(SW5-Pad2)") (class "Default")
      (node (ref "SW5") (pin "2") (pinfunction "2_2") (pintype "unspecified+no_connect"))
    )
    (net (code "80") (name "unconnected-(SW5-Pad3)") (class "Default")
      (node (ref "SW5") (pin "3") (pinfunction "3_3") (pintype "unspecified+no_connect"))
    )
    (net (code "81") (name "unconnected-(U1-AD0-Pad9)") (class "Default")
      (node (ref "U1") (pin "9") (pinfunction "AD0_9") (pintype "unspecified+no_connect"))
    )
    (net (code "82") (name "unconnected-(U1-AUX_CL-Pad7)") (class "Default")
      (node (ref "U1") (pin "7") (pinfunction "AUX_CL_7") (pintype "unspecified+no_connect"))
    )
    (net (code "83") (name "unconnected-(U1-AUX_DA-Pad6)") (class "Default")
      (node (ref "U1") (pin "6") (pinfunction "AUX_DA_6") (pintype "unspecified+no_connect"))
    )
    (net (code "84") (name "unconnected-(U1-CLKIN-Pad1)") (class "Default")
      (node (ref "U1") (pin "1") (pinfunction "CLKIN_1") (pintype "unspecified+no_connect"))
    )
    (net (code "85") (name "unconnected-(U1-EP-Pad25)") (class "Default")
      (node (ref "U1") (pin "25") (pinfunction "EP_25") (pintype "unspecified"))
    )
    (net (code "86") (name "unconnected-(U1-FSYNC-Pad11)") (class "Default")
      (node (ref "U1") (pin "11") (pinfunction "FSYNC_11") (pintype "unspecified+no_connect"))
    )
    (net (code "87") (name "unconnected-(U1-INT-Pad12)") (class "Default")
      (node (ref "U1") (pin "12") (pinfunction "INT_12") (pintype "unspecified+no_connect"))
    )
    (net (code "88") (name "unconnected-(U1-NC-Pad2)") (class "Default")
      (node (ref "U1") (pin "2") (pinfunction "NC_2") (pintype "unspecified+no_connect"))
    )
    (net (code "89") (name "unconnected-(U1-NC-Pad3)") (class "Default")
      (node (ref "U1") (pin "3") (pinfunction "NC_3") (pintype "unspecified+no_connect"))
    )
    (net (code "90") (name "unconnected-(U1-NC-Pad4)") (class "Default")
      (node (ref "U1") (pin "4") (pinfunction "NC_4") (pintype "unspecified+no_connect"))
    )
    (net (code "91") (name "unconnected-(U1-NC-Pad5)") (class "Default")
      (node (ref "U1") (pin "5") (pinfunction "NC_5") (pintype "unspecified+no_connect"))
    )
    (net (code "92") (name "unconnected-(U1-NC-Pad14)") (class "Default")
      (node (ref "U1") (pin "14") (pinfunction "NC_14") (pintype "unspecified+no_connect"))
    )
    (net (code "93") (name "unconnected-(U1-NC-Pad15)") (class "Default")
      (node (ref "U1") (pin "15") (pinfunction "NC_15") (pintype "unspecified+no_connect"))
    )
    (net (code "94") (name "unconnected-(U1-NC-Pad16)") (class "Default")
      (node (ref "U1") (pin "16") (pinfunction "NC_16") (pintype "unspecified+no_connect"))
    )
    (net (code "95") (name "unconnected-(U1-NC-Pad17)") (class "Default")
      (node (ref "U1") (pin "17") (pinfunction "NC_17") (pintype "unspecified+no_connect"))
    )
    (net (code "96") (name "unconnected-(U1-RESV-Pad19)") (class "Default")
      (node (ref "U1") (pin "19") (pinfunction "RESV_19") (pintype "unspecified+no_connect"))
    )
    (net (code "97") (name "unconnected-(U1-RESV-Pad21)") (class "Default")
      (node (ref "U1") (pin "21") (pinfunction "RESV_21") (pintype "unspecified+no_connect"))
    )
    (net (code "98") (name "unconnected-(U1-RESV-Pad22)") (class "Default")
      (node (ref "U1") (pin "22") (pinfunction "RESV_22") (pintype "unspecified+no_connect"))
    )
    (net (code "99") (name "unconnected-(U7-NC-Pad4)") (class "Default")
      (node (ref "U7") (pin "4") (pinfunction "NC_4") (pintype "unspecified+no_connect"))
    )
    (net (code "100") (name "unconnected-(U13-EP-Pad9)") (class "Default")
      (node (ref "U13") (pin "9") (pinfunction "EP_9") (pintype "unspecified"))
    )
    (net (code "101") (name "unconnected-(U14-BST-Pad11)") (class "Default")
      (node (ref "U14") (pin "11") (pinfunction "BST_11") (pintype "unspecified"))
    )
    (net (code "102") (name "unconnected-(U14-NC-Pad10)") (class "Default")
      (node (ref "U14") (pin "10") (pinfunction "NC_10") (pintype "unspecified+no_connect"))
    )
    (net (code "103") (name "unconnected-(U14-NC-Pad15)") (class "Default")
      (node (ref "U14") (pin "15") (pinfunction "NC_15") (pintype "unspecified+no_connect"))
    )
    (net (code "104") (name "unconnected-(U14-PG-Pad18)") (class "Default")
      (node (ref "U14") (pin "18") (pinfunction "PG_18") (pintype "unspecified"))
    )
    (net (code "105") (name "unconnected-(U14-SW-Pad4)") (class "Default")
      (node (ref "U14") (pin "4") (pinfunction "SW_4") (pintype "unspecified"))
    )
    (net (code "106") (name "unconnected-(U14-VCC-Pad2)") (class "Default")
      (node (ref "U14") (pin "2") (pinfunction "VCC_2") (pintype "unspecified+no_connect"))
    )
    (net (code "107") (name "unconnected-(U16-BST-Pad11)") (class "Default")
      (node (ref "U16") (pin "11") (pinfunction "BST_11") (pintype "unspecified"))
    )
    (net (code "108") (name "unconnected-(U16-NC-Pad10)") (class "Default")
      (node (ref "U16") (pin "10") (pinfunction "NC_10") (pintype "unspecified+no_connect"))
    )
    (net (code "109") (name "unconnected-(U16-NC-Pad15)") (class "Default")
      (node (ref "U16") (pin "15") (pinfunction "NC_15") (pintype "unspecified+no_connect"))
    )
    (net (code "110") (name "unconnected-(U16-PG-Pad18)") (class "Default")
      (node (ref "U16") (pin "18") (pinfunction "PG_18") (pintype "unspecified+no_connect"))
    )
    (net (code "111") (name "unconnected-(U16-SW-Pad4)") (class "Default")
      (node (ref "U16") (pin "4") (pinfunction "SW_4") (pintype "unspecified+no_connect"))
    )
    (net (code "112") (name "unconnected-(U16-VCC-Pad2)") (class "Default")
      (node (ref "U16") (pin "2") (pinfunction "VCC_2") (pintype "unspecified+no_connect"))
    )
    (net (code "113") (name "unconnected-(USBC2-SBU1-PadA8)") (class "Default")
      (node (ref "USBC2") (pin "A8") (pinfunction "SBU1_A8") (pintype "unspecified+no_connect"))
    )
    (net (code "114") (name "unconnected-(USBC2-SBU2-PadB8)") (class "Default")
      (node (ref "USBC2") (pin "B8") (pinfunction "SBU2_B8") (pintype "unspecified+no_connect"))
    )
    (net (code "115") (name "unconnected-(X3-GND-Pad2)") (class "Default")
      (node (ref "X3") (pin "2") (pinfunction "GND_2") (pintype "input+no_connect"))
    )
    (net (code "116") (name "unconnected-(X3-GND-Pad4)") (class "Default")
      (node (ref "X3") (pin "4") (pinfunction "GND_4") (pintype "input+no_connect"))
    )
  )
)
